# ST_LINK_V2.net
KiCad netlist of a schematic drawn in Altium Designer
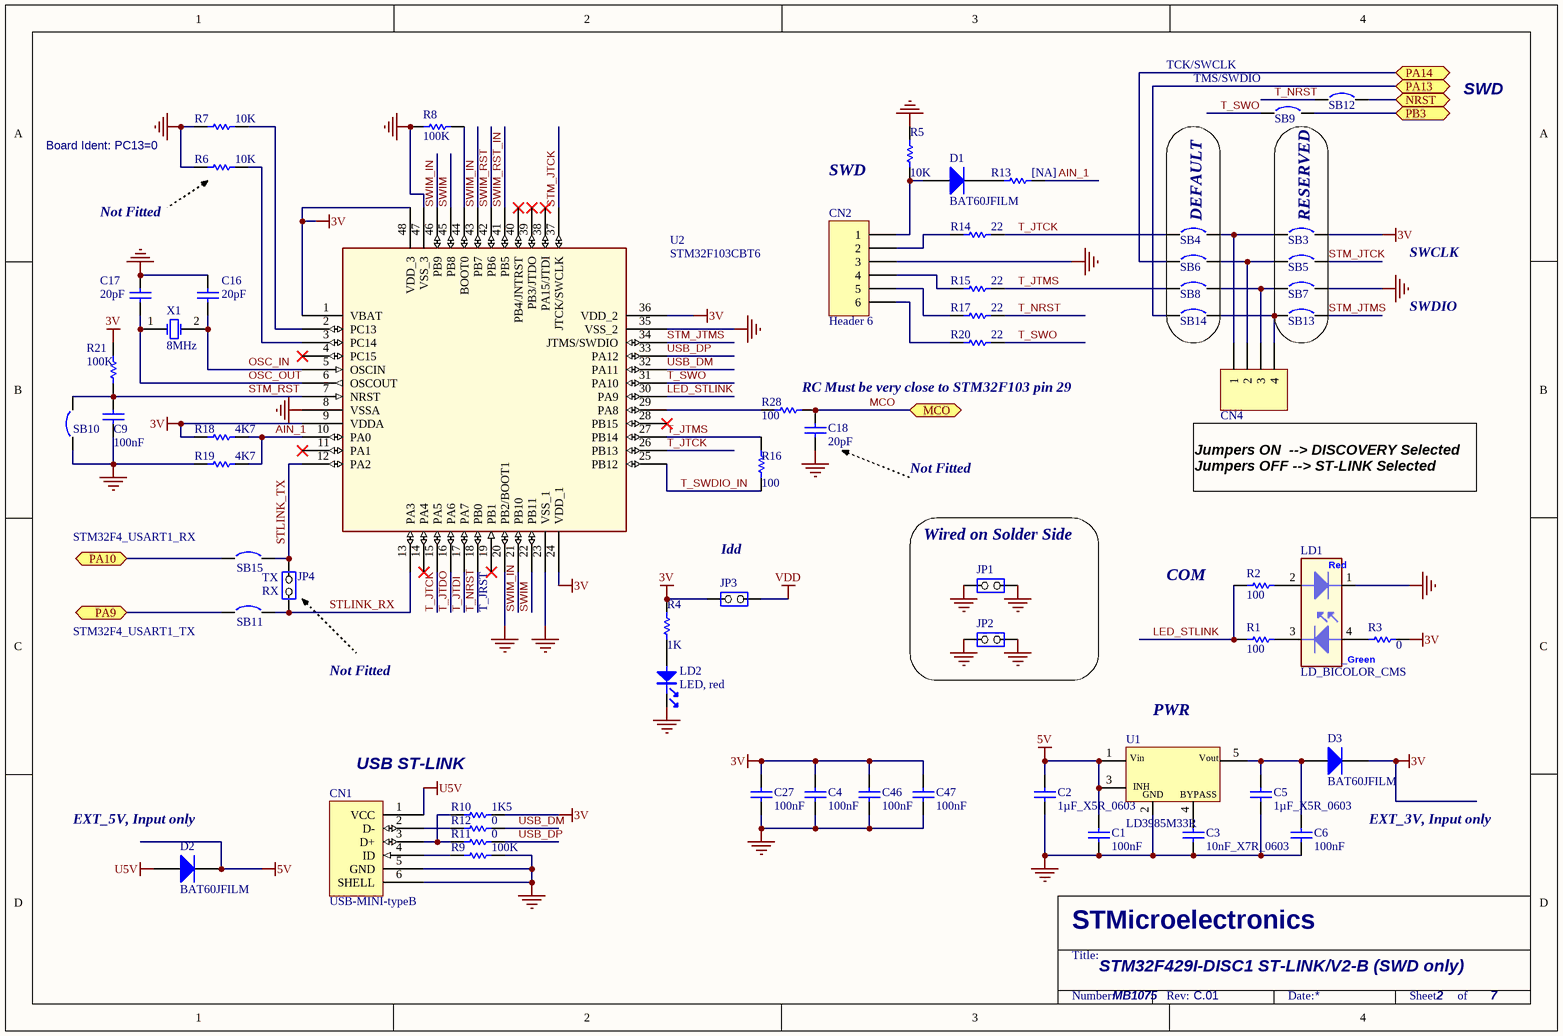
[diagram p0: ST_LINK_V2.SCHDOC]

(export (version "E")
  (design (tool "Eeschema 10.0.6"))
  (components
    (comp (ref "C1")
      (value "100nF")
      (footprint "0402C")
      (description "Capacitor 0402 / 0603 / 0805")
      (libsource (lib "MCD_TOOLS") (part "Capacitor_ST"))
    )
    (comp (ref "C2")
      (value "1µF_X5R_0603")
      (footprint "0603C")
      (description "0603  X5R 1µF")
      (fields (field (name "TOLERANCE") "10%"))
      (libsource (lib "MB963_1") (part "CAP SMD 0603  X5R 1µF 25V 10%"))
    )
    (comp (ref "C3")
      (value "10nF_X7R_0603")
      (footprint "0603C")
      (description "0603  X7R 10NF")
      (fields (field (name "TOLERANCE") "10%"))
      (libsource (lib "MB963_1") (part "CAP SMD 0603  X7R 10000PF 50V 10%"))
    )
    (comp (ref "C4")
      (value "100nF")
      (footprint "0402C")
      (description "Capacitor 0402 / 0603 / 0805")
      (libsource (lib "MCD_TOOLS") (part "Capacitor_ST"))
    )
    (comp (ref "C5")
      (value "1µF_X5R_0603")
      (footprint "0603C")
      (description "0603  X5R 1µF")
      (fields (field (name "TOLERANCE") "10%"))
      (libsource (lib "MB963_1") (part "CAP SMD 0603  X5R 1µF 25V 10%"))
    )
    (comp (ref "C6")
      (value "100nF")
      (footprint "0402C")
      (description "Capacitor 0402 / 0603 / 0805")
      (libsource (lib "MCD_TOOLS") (part "Capacitor_ST"))
    )
    (comp (ref "C9")
      (value "100nF")
      (footprint "0402C")
      (description "Capacitor 0402 / 0603 / 0805")
      (libsource (lib "MCD_TOOLS") (part "Capacitor_ST"))
    )
    (comp (ref "C16")
      (value "20pF")
      (footprint "0402C")
      (description "Capacitor 0402 / 0603 / 0805")
      (libsource (lib "MCD_TOOLS") (part "Capacitor_ST"))
    )
    (comp (ref "C17")
      (value "20pF")
      (footprint "0402C")
      (description "Capacitor 0402 / 0603 / 0805")
      (libsource (lib "MCD_TOOLS") (part "Capacitor_ST"))
    )
    (comp (ref "C18")
      (value "20pF")
      (footprint "0402C")
      (description "Capacitor 0402 / 0603 / 0805")
      (libsource (lib "MCD_TOOLS") (part "Capacitor_ST"))
    )
    (comp (ref "C27")
      (value "100nF")
      (footprint "0402C")
      (description "Capacitor 0402 / 0603 / 0805")
      (libsource (lib "MCD_TOOLS") (part "Capacitor_ST"))
    )
    (comp (ref "C46")
      (value "100nF")
      (footprint "0402C")
      (description "Capacitor 0402 / 0603 / 0805")
      (libsource (lib "MCD_TOOLS") (part "Capacitor_ST"))
    )
    (comp (ref "C47")
      (value "100nF")
      (footprint "0402C")
      (description "Capacitor 0402 / 0603 / 0805")
      (libsource (lib "MCD_TOOLS") (part "Capacitor_ST"))
    )
    (comp (ref "CN1")
      (value "USB-MINI-typeB")
      (footprint "STM-SMEE:USB-MINI-B-SMD")
      (description "USB,MINI-USB-5P/F, 5075BMR-05-M")
      (libsource (lib "MCD_TOOLS") (part "USB-MINI-typeB connector"))
    )
    (comp (ref "CN2")
      (value "Header 6")
      (footprint "HDR1X6")
      (description "Header, 6-Pin")
      (fields (field (name "PUBLISHER") "Altium Limited"))
      (libsource (lib "Miscellaneous Connectors") (part "Header 6"))
    )
    (comp (ref "CN4")
      (value "Header 4")
      (footprint "Header 4")
      (description "Header, 4-Pin")
      (fields (field (name "PUBLISHER") "Altium Limited"))
      (libsource (lib "MB963_1") (part "Header 4"))
    )
    (comp (ref "D1")
      (value "BAT60JFILM")
      (footprint "SOD323/A")
      (libsource (lib "MCD_TOOLS") (part "BAT60JFILM"))
    )
    (comp (ref "D2")
      (value "BAT60JFILM")
      (footprint "SOD323/A")
      (libsource (lib "MCD_TOOLS") (part "BAT60JFILM"))
    )
    (comp (ref "D3")
      (value "BAT60JFILM")
      (footprint "SOD323/A")
      (libsource (lib "MCD_TOOLS") (part "BAT60JFILM"))
    )
    (comp (ref "JP1") (value "~") (footprint "SIP2/2.54") (libsource (lib "*") (part "JP2")))
    (comp (ref "JP2") (value "~") (footprint "SIP2/2.54") (libsource (lib "*") (part "JP2")))
    (comp (ref "JP3") (value "~") (footprint "SIP2/2.54") (libsource (lib "*") (part "JP2")))
    (comp (ref "JP4") (value "JP2") (footprint "SIP2/2.54") (libsource (lib "MCD_TOOLS") (part "JP2")))
    (comp (ref "LD1")
      (value "LD_BICOLOR_CMS")
      (footprint "STM-SMEE:HSMF-A201")
      (description "Bicolor Led")
      (libsource (lib "MCD_TOOLS") (part "LD_BICOLOR_CMS"))
    )
    (comp (ref "LD2")
      (value "LED, red")
      (footprint "0603D")
      (description "LED,red,0603,19-213-R6C-AP1Q2B/3T,everlight")
      (libsource (lib "MCD_TOOLS") (part "LED_red"))
    )
    (comp (ref "R1")
      (value "100")
      (footprint "0402R")
      (description "Resistor 0402 or 0603 or 0805")
      (libsource (lib "MCD_TOOLS") (part "Resistor_ST"))
    )
    (comp (ref "R2")
      (value "100")
      (footprint "0402R")
      (description "Resistor 0402 or 0603 or 0805")
      (libsource (lib "MCD_TOOLS") (part "Resistor_ST"))
    )
    (comp (ref "R3")
      (value "0")
      (footprint "0402R")
      (description "Resistor 0402 or 0603 or 0805")
      (libsource (lib "MCD_TOOLS") (part "Resistor_ST"))
    )
    (comp (ref "R4")
      (value "1K")
      (footprint "0402R")
      (description "Resistor 0402 or 0603 or 0805")
      (libsource (lib "MCD_TOOLS") (part "Resistor_ST"))
    )
    (comp (ref "R5")
      (value "10K")
      (footprint "0402R")
      (description "Resistor 0402 or 0603 or 0805")
      (libsource (lib "MCD_TOOLS") (part "Resistor_ST"))
    )
    (comp (ref "R6")
      (value "10K")
      (footprint "0402R")
      (description "Resistor 0402 or 0603 or 0805")
      (libsource (lib "MCD_TOOLS") (part "Resistor_ST"))
    )
    (comp (ref "R7")
      (value "10K")
      (footprint "0402R")
      (description "Resistor 0402 or 0603 or 0805")
      (libsource (lib "MCD_TOOLS") (part "Resistor_ST"))
    )
    (comp (ref "R8")
      (value "100K")
      (footprint "0402R")
      (description "Resistor 0402 or 0603 or 0805")
      (libsource (lib "MCD_TOOLS") (part "Resistor_ST"))
    )
    (comp (ref "R9")
      (value "100K")
      (footprint "0402R")
      (description "Resistor 0402 or 0603 or 0805")
      (libsource (lib "MCD_TOOLS") (part "Resistor_ST"))
    )
    (comp (ref "R10")
      (value "1K5")
      (footprint "0402R")
      (description "Resistor 0402 or 0603 or 0805")
      (libsource (lib "MCD_TOOLS") (part "Resistor_ST"))
    )
    (comp (ref "R11")
      (value "0")
      (footprint "0402R")
      (description "Resistor 0402 or 0603 or 0805")
      (libsource (lib "MCD_TOOLS") (part "Resistor_ST"))
    )
    (comp (ref "R12")
      (value "0")
      (footprint "0402R")
      (description "Resistor 0402 or 0603 or 0805")
      (libsource (lib "MCD_TOOLS") (part "Resistor_ST"))
    )
    (comp (ref "R13")
      (value "[NA]")
      (footprint "0402R")
      (description "Resistor 0402 or 0603 or 0805")
      (libsource (lib "MCD_TOOLS") (part "Resistor_ST"))
    )
    (comp (ref "R14")
      (value "22")
      (footprint "0402R")
      (description "Resistor 0402 or 0603 or 0805")
      (libsource (lib "MCD_TOOLS") (part "Resistor_ST"))
    )
    (comp (ref "R15")
      (value "22")
      (footprint "0402R")
      (description "Resistor 0402 or 0603 or 0805")
      (libsource (lib "MCD_TOOLS") (part "Resistor_ST"))
    )
    (comp (ref "R16")
      (value "100")
      (footprint "0402R")
      (description "Resistor 0402 or 0603 or 0805")
      (libsource (lib "MCD_TOOLS") (part "Resistor_ST"))
    )
    (comp (ref "R17")
      (value "22")
      (footprint "0402R")
      (description "Resistor 0402 or 0603 or 0805")
      (libsource (lib "MCD_TOOLS") (part "Resistor_ST"))
    )
    (comp (ref "R18")
      (value "4K7")
      (footprint "0402R")
      (description "Resistor 0402 or 0603 or 0805")
      (libsource (lib "MCD_TOOLS") (part "Resistor_ST"))
    )
    (comp (ref "R19")
      (value "4K7")
      (footprint "0402R")
      (description "Resistor 0402 or 0603 or 0805")
      (libsource (lib "MCD_TOOLS") (part "Resistor_ST"))
    )
    (comp (ref "R20")
      (value "22")
      (footprint "0402R")
      (description "Resistor 0402 or 0603 or 0805")
      (libsource (lib "MCD_TOOLS") (part "Resistor_ST"))
    )
    (comp (ref "R21")
      (value "100K")
      (footprint "0402R")
      (description "Resistor 0402 or 0603 or 0805")
      (libsource (lib "MCD_TOOLS") (part "Resistor_ST"))
    )
    (comp (ref "R28")
      (value "100")
      (footprint "0402R")
      (description "Resistor 0402 or 0603 or 0805")
      (libsource (lib "MCD_TOOLS") (part "Resistor_ST"))
    )
    (comp (ref "SB3")
      (value "Circuit Breaker")
      (footprint "JP2_SMD")
      (fields (field (name "PUBLISHER") "Altium Limited"))
      (libsource (lib "MB915") (part "Circuit Breaker"))
    )
    (comp (ref "SB4")
      (value "Circuit Breaker")
      (footprint "JP2_SMD")
      (fields (field (name "PUBLISHER") "Altium Limited"))
      (libsource (lib "MB915") (part "Circuit Breaker"))
    )
    (comp (ref "SB5")
      (value "Circuit Breaker")
      (footprint "JP2_SMD")
      (fields (field (name "PUBLISHER") "Altium Limited"))
      (libsource (lib "MB915") (part "Circuit Breaker"))
    )
    (comp (ref "SB6")
      (value "Circuit Breaker")
      (footprint "JP2_SMD")
      (fields (field (name "PUBLISHER") "Altium Limited"))
      (libsource (lib "MB915") (part "Circuit Breaker"))
    )
    (comp (ref "SB7")
      (value "Circuit Breaker")
      (footprint "JP2_SMD")
      (fields (field (name "PUBLISHER") "Altium Limited"))
      (libsource (lib "MB915") (part "Circuit Breaker"))
    )
    (comp (ref "SB8")
      (value "Circuit Breaker")
      (footprint "JP2_SMD")
      (fields (field (name "PUBLISHER") "Altium Limited"))
      (libsource (lib "MB915") (part "Circuit Breaker"))
    )
    (comp (ref "SB9")
      (value "Circuit Breaker")
      (footprint "JP2_SMD")
      (fields (field (name "PUBLISHER") "Altium Limited"))
      (libsource (lib "MCD_TOOLS") (part "Circuit Breaker"))
    )
    (comp (ref "SB10")
      (value "Circuit Breaker")
      (footprint "JP2_SMD")
      (fields (field (name "PUBLISHER") "Altium Limited"))
      (libsource (lib "MB915") (part "Circuit Breaker"))
    )
    (comp (ref "SB11")
      (value "Circuit Breaker")
      (footprint "JP2_SMD")
      (fields (field (name "PUBLISHER") "Altium Limited"))
      (libsource (lib "MCD_TOOLS") (part "Circuit Breaker"))
    )
    (comp (ref "SB12")
      (value "Circuit Breaker")
      (footprint "JP2_SMD")
      (fields (field (name "PUBLISHER") "Altium Limited"))
      (libsource (lib "MB915") (part "Circuit Breaker"))
    )
    (comp (ref "SB13")
      (value "Circuit Breaker")
      (footprint "JP2_SMD")
      (fields (field (name "PUBLISHER") "Altium Limited"))
      (libsource (lib "MB915") (part "Circuit Breaker"))
    )
    (comp (ref "SB14")
      (value "Circuit Breaker")
      (footprint "JP2_SMD")
      (fields (field (name "PUBLISHER") "Altium Limited"))
      (libsource (lib "MB915") (part "Circuit Breaker"))
    )
    (comp (ref "SB15")
      (value "Circuit Breaker")
      (footprint "JP2_SMD")
      (fields (field (name "PUBLISHER") "Altium Limited"))
      (libsource (lib "MCD_TOOLS") (part "Circuit Breaker"))
    )
    (comp (ref "U1")
      (value "LD3985M33R")
      (footprint "STM-SMEE:SOT-23-5L")
      (description "Ultra low drop-low noise BiCMOS voltage, regulators low ESR capacitors compatible")
      (libsource (lib "MCD_TOOLS") (part "LD3985M33R"))
    )
    (comp (ref "U2")
      (value "STM32F103CBT6")
      (footprint "QFP48 7x7")
      (description "Medium-density performance line ARM-based 32-bit MCU with 128KB Flash")
      (libsource (lib "MCD_TOOLS") (part "STM32F103CBT6"))
    )
    (comp (ref "X1")
      (value "8MHz")
      (footprint "STM-SMEE:XTAL1")
      (description "Crystal Oscillator,8Mhz,20PF,20PPM,-10-70 degree,DIP,HC-49S")
      (libsource (lib "MCD_TOOLS") (part "XTAL"))
    )
  )
  (nets
    (net (code "1") (name "/AIN_1") (class "Default")
      (node (ref "R13") (pin "2") (pinfunction "2_2") (pintype "passive"))
      (node (ref "R18") (pin "2") (pinfunction "2_2") (pintype "passive"))
      (node (ref "R19") (pin "2") (pinfunction "2_2") (pintype "passive"))
      (node (ref "U2") (pin "10") (pinfunction "PA0_10") (pintype "bidirectional"))
    )
    (net (code "2") (name "/LED_STLINK") (class "Default")
      (node (ref "R1") (pin "1") (pinfunction "1_1") (pintype "passive"))
      (node (ref "R2") (pin "1") (pinfunction "1_1") (pintype "passive"))
      (node (ref "U2") (pin "30") (pinfunction "PA9_30") (pintype "bidirectional"))
    )
    (net (code "3") (name "/MCO") (class "Default")
      (node (ref "C18") (pin "2") (pinfunction "2_2") (pintype "passive"))
      (node (ref "R28") (pin "2") (pinfunction "2_2") (pintype "passive"))
    )
    (net (code "4") (name "/NRST") (class "Default")
      (node (ref "SB12") (pin "2") (pinfunction "2_2") (pintype "passive"))
    )
    (net (code "5") (name "/OSC_IN") (class "Default")
      (node (ref "C16") (pin "1") (pinfunction "1_1") (pintype "passive"))
      (node (ref "U2") (pin "5") (pinfunction "OSCIN_5") (pintype "input"))
      (node (ref "X1") (pin "2") (pinfunction "OSC2_2") (pintype "passive"))
    )
    (net (code "6") (name "/OSC_OUT") (class "Default")
      (node (ref "C17") (pin "1") (pinfunction "1_1") (pintype "passive"))
      (node (ref "U2") (pin "6") (pinfunction "OSCOUT_6") (pintype "output"))
      (node (ref "X1") (pin "1") (pinfunction "OSC1_1") (pintype "passive"))
    )
    (net (code "7") (name "/PA9") (class "Default")
      (node (ref "SB11") (pin "1") (pinfunction "1_1") (pintype "passive"))
    )
    (net (code "8") (name "/PA10") (class "Default")
      (node (ref "SB15") (pin "1") (pinfunction "1_1") (pintype "passive"))
    )
    (net (code "9") (name "/PA13") (class "Default")
      (node (ref "SB14") (pin "1") (pinfunction "1_1") (pintype "passive"))
    )
    (net (code "10") (name "/PA14") (class "Default")
      (node (ref "SB6") (pin "1") (pinfunction "1_1") (pintype "passive"))
    )
    (net (code "11") (name "/PB3") (class "Default")
      (node (ref "SB9") (pin "2") (pinfunction "2_2") (pintype "passive"))
    )
    (net (code "12") (name "/STLINK_RX") (class "Default")
      (node (ref "JP4") (pin "1") (pinfunction "COMMON_1") (pintype "passive"))
      (node (ref "SB11") (pin "2") (pinfunction "2_2") (pintype "passive"))
      (node (ref "U2") (pin "13") (pinfunction "PA3_13") (pintype "bidirectional"))
    )
    (net (code "13") (name "/STLINK_TX") (class "Default")
      (node (ref "JP4") (pin "2") (pinfunction "NO_2") (pintype "passive"))
      (node (ref "SB15") (pin "2") (pinfunction "2_2") (pintype "passive"))
      (node (ref "U2") (pin "12") (pinfunction "PA2_12") (pintype "bidirectional"))
    )
    (net (code "14") (name "/STM_JTCK") (class "Default")
      (node (ref "SB5") (pin "2") (pinfunction "2_2") (pintype "passive"))
      (node (ref "U2") (pin "37") (pinfunction "JTCK/SWCLK_37") (pintype "bidirectional"))
    )
    (net (code "15") (name "/STM_JTMS") (class "Default")
      (node (ref "SB13") (pin "2") (pinfunction "2_2") (pintype "passive"))
      (node (ref "U2") (pin "34") (pinfunction "JTMS/SWDIO_34") (pintype "bidirectional"))
    )
    (net (code "16") (name "/STM_RST") (class "Default")
      (node (ref "C9") (pin "2") (pinfunction "2_2") (pintype "passive"))
      (node (ref "R21") (pin "1") (pinfunction "1_1") (pintype "passive"))
      (node (ref "SB10") (pin "2") (pinfunction "2_2") (pintype "passive"))
      (node (ref "U2") (pin "7") (pinfunction "NRST_7") (pintype "input"))
    )
    (net (code "17") (name "/SWIM") (class "Default")
      (node (ref "U2") (pin "22") (pinfunction "PB11_22") (pintype "bidirectional"))
      (node (ref "U2") (pin "45") (pinfunction "PB8_45") (pintype "bidirectional"))
    )
    (net (code "18") (name "/SWIM_IN") (class "Default")
      (node (ref "U2") (pin "21") (pinfunction "PB10_21") (pintype "bidirectional"))
      (node (ref "U2") (pin "43") (pinfunction "PB7_43") (pintype "bidirectional"))
      (node (ref "U2") (pin "46") (pinfunction "PB9_46") (pintype "bidirectional"))
    )
    (net (code "19") (name "/SWIM_RST") (class "Default")
      (node (ref "U2") (pin "42") (pinfunction "PB6_42") (pintype "bidirectional"))
    )
    (net (code "20") (name "/SWIM_RST_IN") (class "Default")
      (node (ref "U2") (pin "41") (pinfunction "PB5_41") (pintype "bidirectional"))
    )
    (net (code "21") (name "/T_JTCK") (class "Default")
      (node (ref "R14") (pin "2") (pinfunction "2_2") (pintype "passive"))
      (node (ref "SB4") (pin "1") (pinfunction "1_1") (pintype "passive"))
      (node (ref "U2") (pin "15") (pinfunction "PA5_15") (pintype "bidirectional"))
      (node (ref "U2") (pin "26") (pinfunction "PB13_26") (pintype "bidirectional"))
    )
    (net (code "22") (name "/T_JTDI") (class "Default")
      (node (ref "U2") (pin "17") (pinfunction "PA7_17") (pintype "bidirectional"))
    )
    (net (code "23") (name "/T_JTDO") (class "Default")
      (node (ref "U2") (pin "16") (pinfunction "PA6_16") (pintype "bidirectional"))
    )
    (net (code "24") (name "/T_JTMS") (class "Default")
      (node (ref "R15") (pin "2") (pinfunction "2_2") (pintype "passive"))
      (node (ref "R16") (pin "2") (pinfunction "2_2") (pintype "passive"))
      (node (ref "SB8") (pin "1") (pinfunction "1_1") (pintype "passive"))
      (node (ref "U2") (pin "27") (pinfunction "PB14_27") (pintype "bidirectional"))
    )
    (net (code "25") (name "/T_NRST") (class "Default")
      (node (ref "R17") (pin "2") (pinfunction "2_2") (pintype "passive"))
      (node (ref "SB12") (pin "1") (pinfunction "1_1") (pintype "passive"))
      (node (ref "U2") (pin "18") (pinfunction "PB0_18") (pintype "bidirectional"))
    )
    (net (code "26") (name "/T_SWDIO_IN") (class "Default")
      (node (ref "R16") (pin "1") (pinfunction "1_1") (pintype "passive"))
      (node (ref "U2") (pin "25") (pinfunction "PB12_25") (pintype "bidirectional"))
    )
    (net (code "27") (name "/T_SWO") (class "Default")
      (node (ref "R20") (pin "2") (pinfunction "2_2") (pintype "passive"))
      (node (ref "SB9") (pin "1") (pinfunction "1_1") (pintype "passive"))
      (node (ref "U2") (pin "31") (pinfunction "PA10_31") (pintype "bidirectional"))
    )
    (net (code "28") (name "/USB_DM") (class "Default")
      (node (ref "R12") (pin "2") (pinfunction "2_2") (pintype "passive"))
      (node (ref "U2") (pin "32") (pinfunction "PA11_32") (pintype "bidirectional"))
    )
    (net (code "29") (name "/USB_DP") (class "Default")
      (node (ref "R11") (pin "2") (pinfunction "2_2") (pintype "passive"))
      (node (ref "U2") (pin "33") (pinfunction "PA12_33") (pintype "bidirectional"))
    )
    (net (code "30") (name "3V") (class "Default")
      (node (ref "C27") (pin "2") (pinfunction "2_2") (pintype "passive"))
      (node (ref "C4") (pin "2") (pinfunction "2_2") (pintype "passive"))
      (node (ref "C46") (pin "2") (pinfunction "2_2") (pintype "passive"))
      (node (ref "C47") (pin "2") (pinfunction "2_2") (pintype "passive"))
      (node (ref "D3") (pin "2") (pinfunction "K_2") (pintype "passive"))
      (node (ref "JP3") (pin "1") (pinfunction "COMMON_1") (pintype "passive"))
      (node (ref "R10") (pin "2") (pinfunction "2_2") (pintype "passive"))
      (node (ref "R18") (pin "1") (pinfunction "1_1") (pintype "passive"))
      (node (ref "R21") (pin "2") (pinfunction "2_2") (pintype "passive"))
      (node (ref "R3") (pin "2") (pinfunction "2_2") (pintype "passive"))
      (node (ref "R4") (pin "2") (pinfunction "2_2") (pintype "passive"))
      (node (ref "SB3") (pin "2") (pinfunction "2_2") (pintype "passive"))
      (node (ref "U2") (pin "1") (pinfunction "VBAT_1") (pintype "power_in"))
      (node (ref "U2") (pin "24") (pinfunction "VDD_1_24") (pintype "power_in"))
      (node (ref "U2") (pin "36") (pinfunction "VDD_2_36") (pintype "power_in"))
      (node (ref "U2") (pin "48") (pinfunction "VDD_3_48") (pintype "power_in"))
      (node (ref "U2") (pin "9") (pinfunction "VDDA_9") (pintype "power_in"))
    )
    (net (code "31") (name "5V") (class "Default")
      (node (ref "C1") (pin "2") (pinfunction "2_2") (pintype "passive"))
      (node (ref "C2") (pin "2") (pinfunction "2_2") (pintype "passive"))
      (node (ref "D2") (pin "2") (pinfunction "K_2") (pintype "passive"))
      (node (ref "U1") (pin "1") (pinfunction "Vin_1") (pintype "passive"))
      (node (ref "U1") (pin "3") (pinfunction "CE_3") (pintype "passive"))
    )
    (net (code "32") (name "GND") (class "Default")
      (node (ref "C1") (pin "1") (pinfunction "1_1") (pintype "passive"))
      (node (ref "C16") (pin "2") (pinfunction "2_2") (pintype "passive"))
      (node (ref "C17") (pin "2") (pinfunction "2_2") (pintype "passive"))
      (node (ref "C18") (pin "1") (pinfunction "1_1") (pintype "passive"))
      (node (ref "C2") (pin "1") (pinfunction "1_1") (pintype "passive"))
      (node (ref "C27") (pin "1") (pinfunction "1_1") (pintype "passive"))
      (node (ref "C3") (pin "1") (pinfunction "1_1") (pintype "passive"))
      (node (ref "C4") (pin "1") (pinfunction "1_1") (pintype "passive"))
      (node (ref "C46") (pin "1") (pinfunction "1_1") (pintype "passive"))
      (node (ref "C47") (pin "1") (pinfunction "1_1") (pintype "passive"))
      (node (ref "C5") (pin "2") (pinfunction "2_2") (pintype "passive"))
      (node (ref "C6") (pin "1") (pinfunction "1_1") (pintype "passive"))
      (node (ref "C9") (pin "1") (pinfunction "1_1") (pintype "passive"))
      (node (ref "CN1") (pin "5") (pinfunction "GND_5") (pintype "passive"))
      (node (ref "CN1") (pin "6") (pinfunction "SHELL_6") (pintype "passive"))
      (node (ref "CN2") (pin "3") (pinfunction "3_3") (pintype "passive"))
      (node (ref "JP1") (pin "1") (pinfunction "COMMON_1") (pintype "passive"))
      (node (ref "JP1") (pin "2") (pinfunction "NO_2") (pintype "passive"))
      (node (ref "JP2") (pin "1") (pinfunction "COMMON_1") (pintype "passive"))
      (node (ref "JP2") (pin "2") (pinfunction "NO_2") (pintype "passive"))
      (node (ref "LD1") (pin "1") (pinfunction "1_1") (pintype "passive"))
      (node (ref "LD2") (pin "2") (pintype "passive"))
      (node (ref "R19") (pin "1") (pinfunction "1_1") (pintype "passive"))
      (node (ref "R5") (pin "2") (pinfunction "2_2") (pintype "passive"))
      (node (ref "R6") (pin "1") (pinfunction "1_1") (pintype "passive"))
      (node (ref "R7") (pin "1") (pinfunction "1_1") (pintype "passive"))
      (node (ref "R8") (pin "1") (pinfunction "1_1") (pintype "passive"))
      (node (ref "R9") (pin "2") (pinfunction "2_2") (pintype "passive"))
      (node (ref "SB10") (pin "1") (pinfunction "1_1") (pintype "passive"))
      (node (ref "SB7") (pin "2") (pinfunction "2_2") (pintype "passive"))
      (node (ref "U1") (pin "2") (pinfunction "GND_2") (pintype "passive"))
      (node (ref "U2") (pin "20") (pinfunction "PB2/BOOT1_20") (pintype "bidirectional"))
      (node (ref "U2") (pin "23") (pinfunction "VSS_1_23") (pintype "power_in"))
      (node (ref "U2") (pin "35") (pinfunction "VSS_2_35") (pintype "power_in"))
      (node (ref "U2") (pin "47") (pinfunction "VSS_3_47") (pintype "power_in"))
      (node (ref "U2") (pin "8") (pinfunction "VSSA_8") (pintype "power_in"))
    )
    (net (code "33") (name "Net-(CN1-D+)") (class "Default")
      (node (ref "CN1") (pin "3") (pinfunction "D+_3") (pintype "bidirectional"))
      (node (ref "R10") (pin "1") (pinfunction "1_1") (pintype "passive"))
      (node (ref "R11") (pin "1") (pinfunction "1_1") (pintype "passive"))
    )
    (net (code "34") (name "Net-(CN1-D-)") (class "Default")
      (node (ref "CN1") (pin "2") (pinfunction "D-_2") (pintype "bidirectional"))
      (node (ref "R12") (pin "1") (pinfunction "1_1") (pintype "passive"))
    )
    (net (code "35") (name "Net-(CN1-ID)") (class "Default")
      (node (ref "CN1") (pin "4") (pinfunction "ID_4") (pintype "input"))
      (node (ref "R9") (pin "1") (pinfunction "1_1") (pintype "passive"))
    )
    (net (code "36") (name "Net-(CN2-Pad2)") (class "Default")
      (node (ref "CN2") (pin "2") (pinfunction "2_2") (pintype "passive"))
      (node (ref "R14") (pin "1") (pinfunction "1_1") (pintype "passive"))
    )
    (net (code "37") (name "Net-(CN2-Pad4)") (class "Default")
      (node (ref "CN2") (pin "4") (pinfunction "4_4") (pintype "passive"))
      (node (ref "R15") (pin "1") (pinfunction "1_1") (pintype "passive"))
    )
    (net (code "38") (name "Net-(CN2-Pad5)") (class "Default")
      (node (ref "CN2") (pin "5") (pinfunction "5_5") (pintype "passive"))
      (node (ref "R17") (pin "1") (pinfunction "1_1") (pintype "passive"))
    )
    (net (code "39") (name "Net-(CN2-Pad6)") (class "Default")
      (node (ref "CN2") (pin "6") (pinfunction "6_6") (pintype "passive"))
      (node (ref "R20") (pin "1") (pinfunction "1_1") (pintype "passive"))
    )
    (net (code "40") (name "Net-(CN4-Pad1)") (class "Default")
      (node (ref "CN4") (pin "1") (pinfunction "1_1") (pintype "passive"))
      (node (ref "SB3") (pin "1") (pinfunction "1_1") (pintype "passive"))
      (node (ref "SB4") (pin "2") (pinfunction "2_2") (pintype "passive"))
    )
    (net (code "41") (name "Net-(CN4-Pad2)") (class "Default")
      (node (ref "CN4") (pin "2") (pinfunction "2_2") (pintype "passive"))
      (node (ref "SB5") (pin "1") (pinfunction "1_1") (pintype "passive"))
      (node (ref "SB6") (pin "2") (pinfunction "2_2") (pintype "passive"))
    )
    (net (code "42") (name "Net-(CN4-Pad3)") (class "Default")
      (node (ref "CN4") (pin "3") (pinfunction "3_3") (pintype "passive"))
      (node (ref "SB7") (pin "1") (pinfunction "1_1") (pintype "passive"))
      (node (ref "SB8") (pin "2") (pinfunction "2_2") (pintype "passive"))
    )
    (net (code "43") (name "Net-(CN4-Pad4)") (class "Default")
      (node (ref "CN4") (pin "4") (pinfunction "4_4") (pintype "passive"))
      (node (ref "SB13") (pin "1") (pinfunction "1_1") (pintype "passive"))
      (node (ref "SB14") (pin "2") (pinfunction "2_2") (pintype "passive"))
    )
    (net (code "44") (name "Net-(D1-A)") (class "Default")
      (node (ref "CN2") (pin "1") (pinfunction "1_1") (pintype "passive"))
      (node (ref "D1") (pin "1") (pinfunction "A_1") (pintype "passive"))
      (node (ref "R5") (pin "1") (pinfunction "1_1") (pintype "passive"))
    )
    (net (code "45") (name "Net-(D1-K)") (class "Default")
      (node (ref "D1") (pin "2") (pinfunction "K_2") (pintype "passive"))
      (node (ref "R13") (pin "1") (pinfunction "1_1") (pintype "passive"))
    )
    (net (code "46") (name "Net-(D3-A)") (class "Default")
      (node (ref "C5") (pin "1") (pinfunction "1_1") (pintype "passive"))
      (node (ref "C6") (pin "2") (pinfunction "2_2") (pintype "passive"))
      (node (ref "D3") (pin "1") (pinfunction "A_1") (pintype "passive"))
      (node (ref "U1") (pin "5") (pinfunction "Vout_5") (pintype "passive"))
    )
    (net (code "47") (name "Net-(LD1-Pad2)") (class "Default")
      (node (ref "LD1") (pin "2") (pinfunction "2_2") (pintype "passive"))
      (node (ref "R2") (pin "2") (pinfunction "2_2") (pintype "passive"))
    )
    (net (code "48") (name "Net-(LD1-Pad3)") (class "Default")
      (node (ref "LD1") (pin "3") (pinfunction "3_3") (pintype "passive"))
      (node (ref "R1") (pin "2") (pinfunction "2_2") (pintype "passive"))
    )
    (net (code "49") (name "Net-(LD1-Pad4)") (class "Default")
      (node (ref "LD1") (pin "4") (pinfunction "4_4") (pintype "passive"))
      (node (ref "R3") (pin "1") (pinfunction "1_1") (pintype "passive"))
    )
    (net (code "50") (name "Net-(LD2-Pad1)") (class "Default")
      (node (ref "LD2") (pin "1") (pintype "passive"))
      (node (ref "R4") (pin "1") (pinfunction "1_1") (pintype "passive"))
    )
    (net (code "51") (name "Net-(U1-BYPASS)") (class "Default")
      (node (ref "C3") (pin "2") (pinfunction "2_2") (pintype "passive"))
      (node (ref "U1") (pin "4") (pinfunction "BYPASS_4") (pintype "passive"))
    )
    (net (code "52") (name "Net-(U2-BOOT0)") (class "Default")
      (node (ref "R8") (pin "2") (pinfunction "2_2") (pintype "passive"))
      (node (ref "U2") (pin "44") (pinfunction "BOOT0_44") (pintype "bidirectional"))
    )
    (net (code "53") (name "Net-(U2-PA8)") (class "Default")
      (node (ref "R28") (pin "1") (pinfunction "1_1") (pintype "passive"))
      (node (ref "U2") (pin "29") (pinfunction "PA8_29") (pintype "bidirectional"))
    )
    (net (code "54") (name "Net-(U2-PC13)") (class "Default")
      (node (ref "R7") (pin "2") (pinfunction "2_2") (pintype "passive"))
      (node (ref "U2") (pin "2") (pinfunction "PC13_2") (pintype "bidirectional"))
    )
    (net (code "55") (name "Net-(U2-PC14)") (class "Default")
      (node (ref "R6") (pin "2") (pinfunction "2_2") (pintype "passive"))
      (node (ref "U2") (pin "3") (pinfunction "PC14_3") (pintype "bidirectional"))
    )
    (net (code "56") (name "U5V") (class "Default")
      (node (ref "CN1") (pin "1") (pinfunction "VCC_1") (pintype "power_in"))
      (node (ref "D2") (pin "1") (pinfunction "A_1") (pintype "passive"))
    )
    (net (code "57") (name "VDD") (class "Default")
      (node (ref "JP3") (pin "2") (pinfunction "NO_2") (pintype "passive"))
    )
    (net (code "58") (name "unconnected-(U2-PA1-Pad11)") (class "Default")
      (node (ref "U2") (pin "11") (pinfunction "PA1_11") (pintype "bidirectional+no_connect"))
    )
    (net (code "59") (name "unconnected-(U2-PA4-Pad14)") (class "Default")
      (node (ref "U2") (pin "14") (pinfunction "PA4_14") (pintype "bidirectional+no_connect"))
    )
    (net (code "60") (name "unconnected-(U2-PA15{slash}JTDI-Pad38)") (class "Default")
      (node (ref "U2") (pin "38") (pinfunction "PA15/JTDI_38") (pintype "bidirectional+no_connect"))
    )
    (net (code "61") (name "unconnected-(U2-PB1-Pad19)") (class "Default")
      (node (ref "U2") (pin "19") (pinfunction "PB1_19") (pintype "input+no_connect"))
    )
    (net (code "62") (name "unconnected-(U2-PB3{slash}JTDO-Pad39)") (class "Default")
      (node (ref "U2") (pin "39") (pinfunction "PB3/JTDO_39") (pintype "bidirectional+no_connect"))
    )
    (net (code "63") (name "unconnected-(U2-PB4{slash}JNTRST-Pad40)") (class "Default")
      (node (ref "U2") (pin "40") (pinfunction "PB4/JNTRST_40") (pintype "bidirectional+no_connect"))
    )
    (net (code "64") (name "unconnected-(U2-PB15-Pad28)") (class "Default")
      (node (ref "U2") (pin "28") (pinfunction "PB15_28") (pintype "bidirectional+no_connect"))
    )
    (net (code "65") (name "unconnected-(U2-PC15-Pad4)") (class "Default")
      (node (ref "U2") (pin "4") (pinfunction "PC15_4") (pintype "bidirectional+no_connect"))
    )
  )
)
